# Iridium_Carrier_2.net
KiCad netlist of a schematic drawn in EAGLE
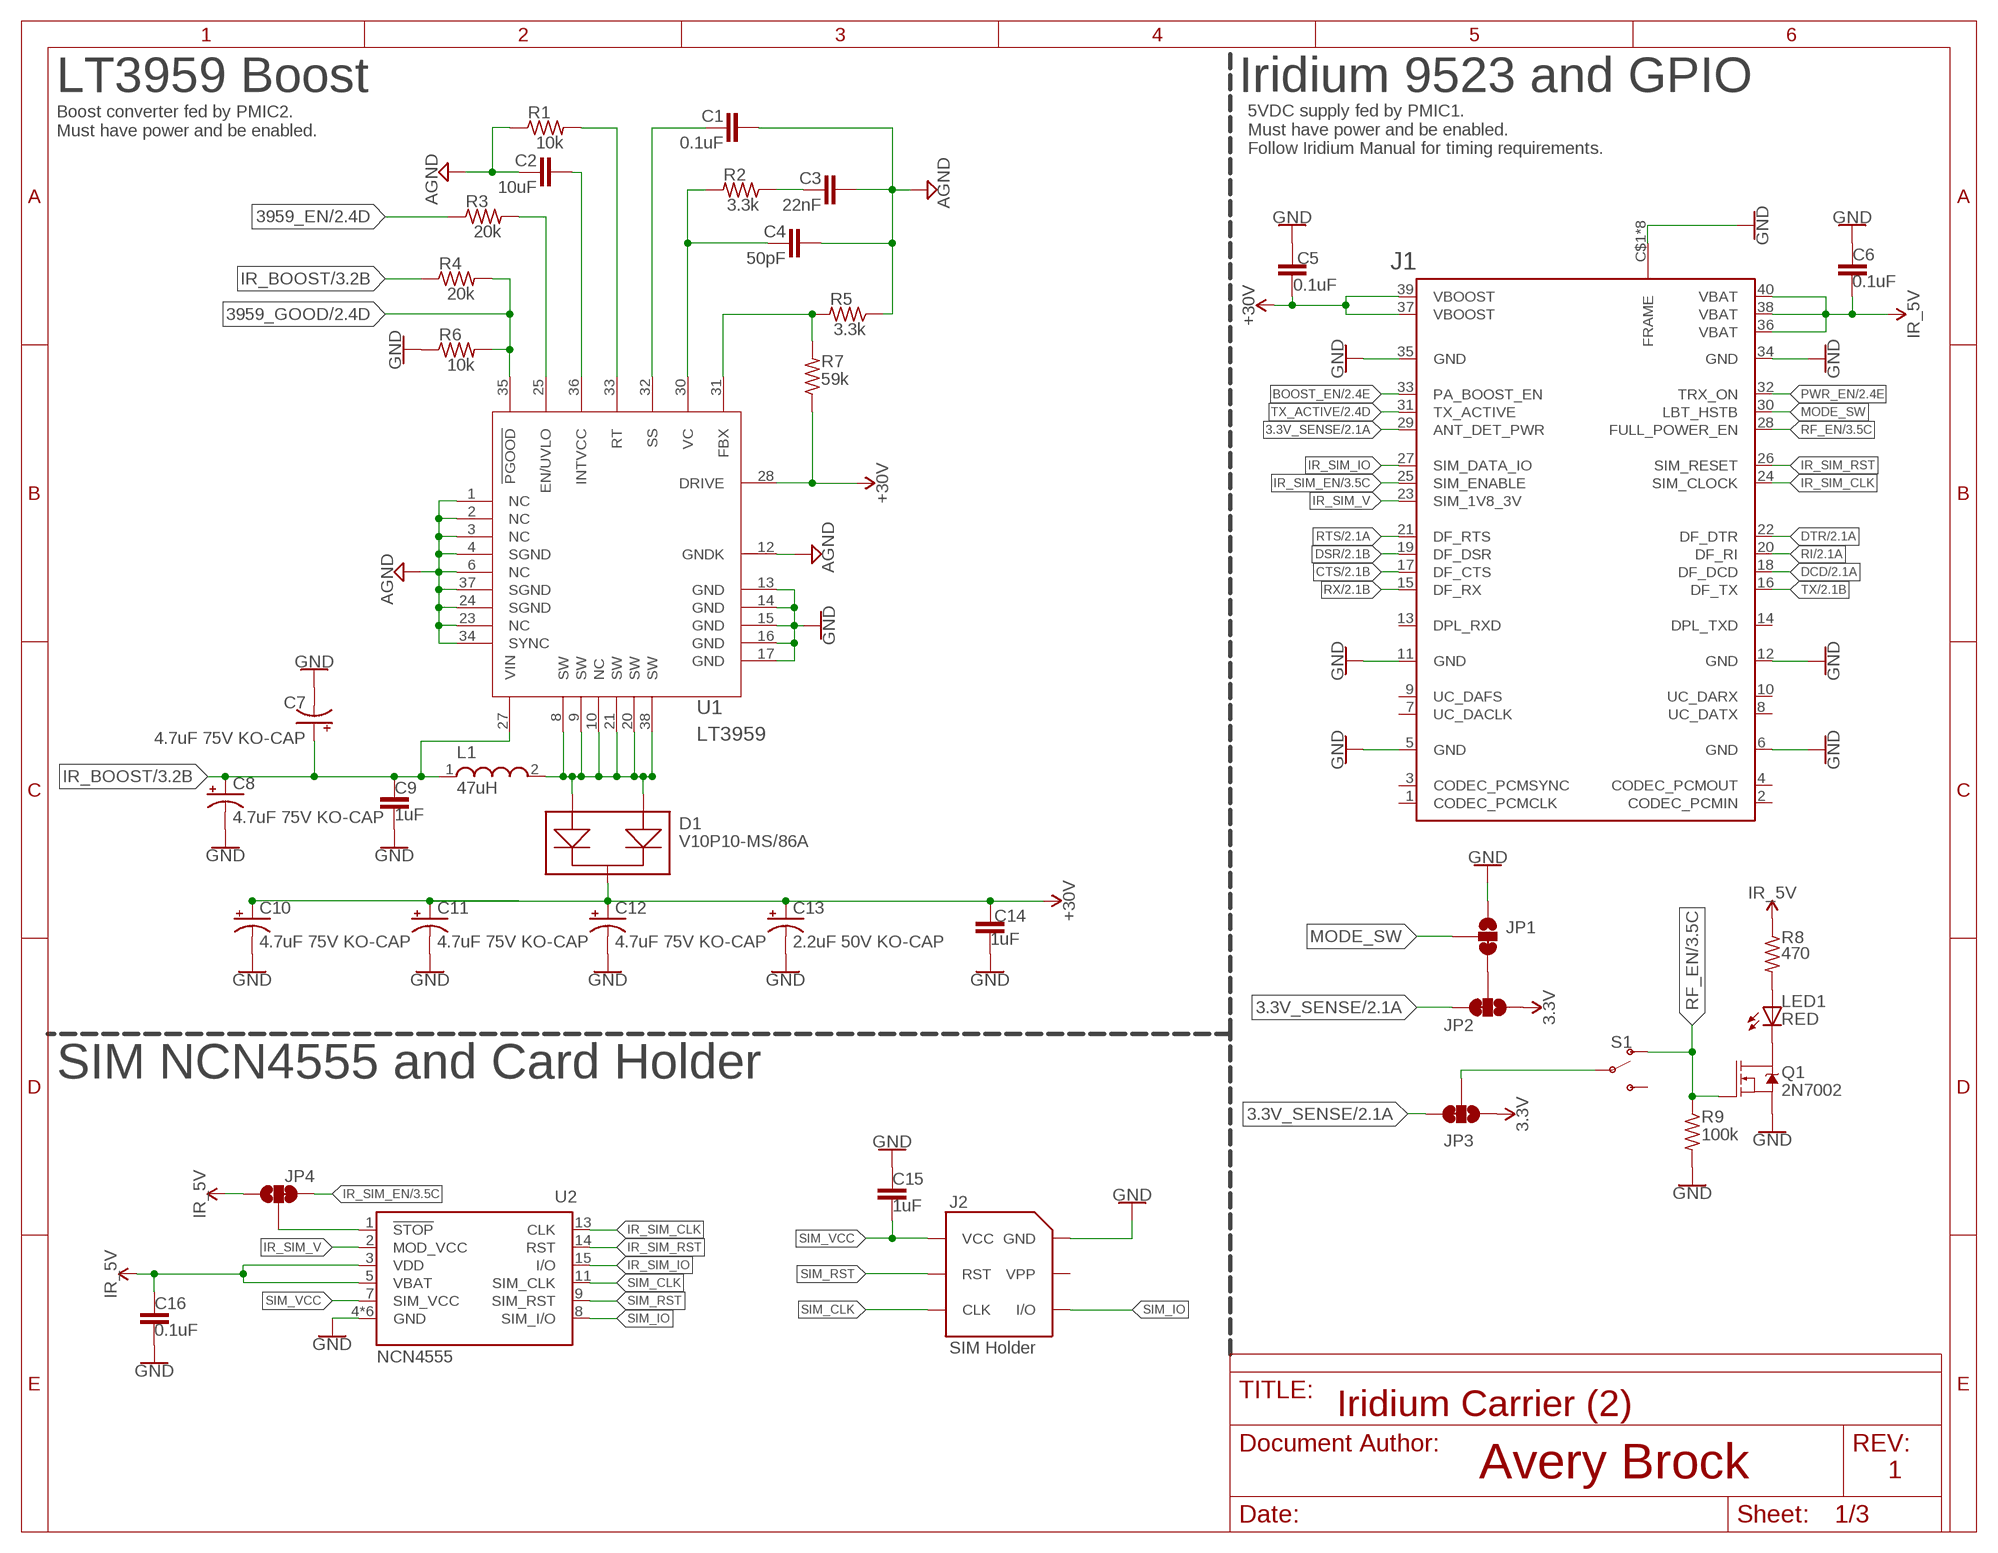
[diagram p0: schematic, sheet 1]
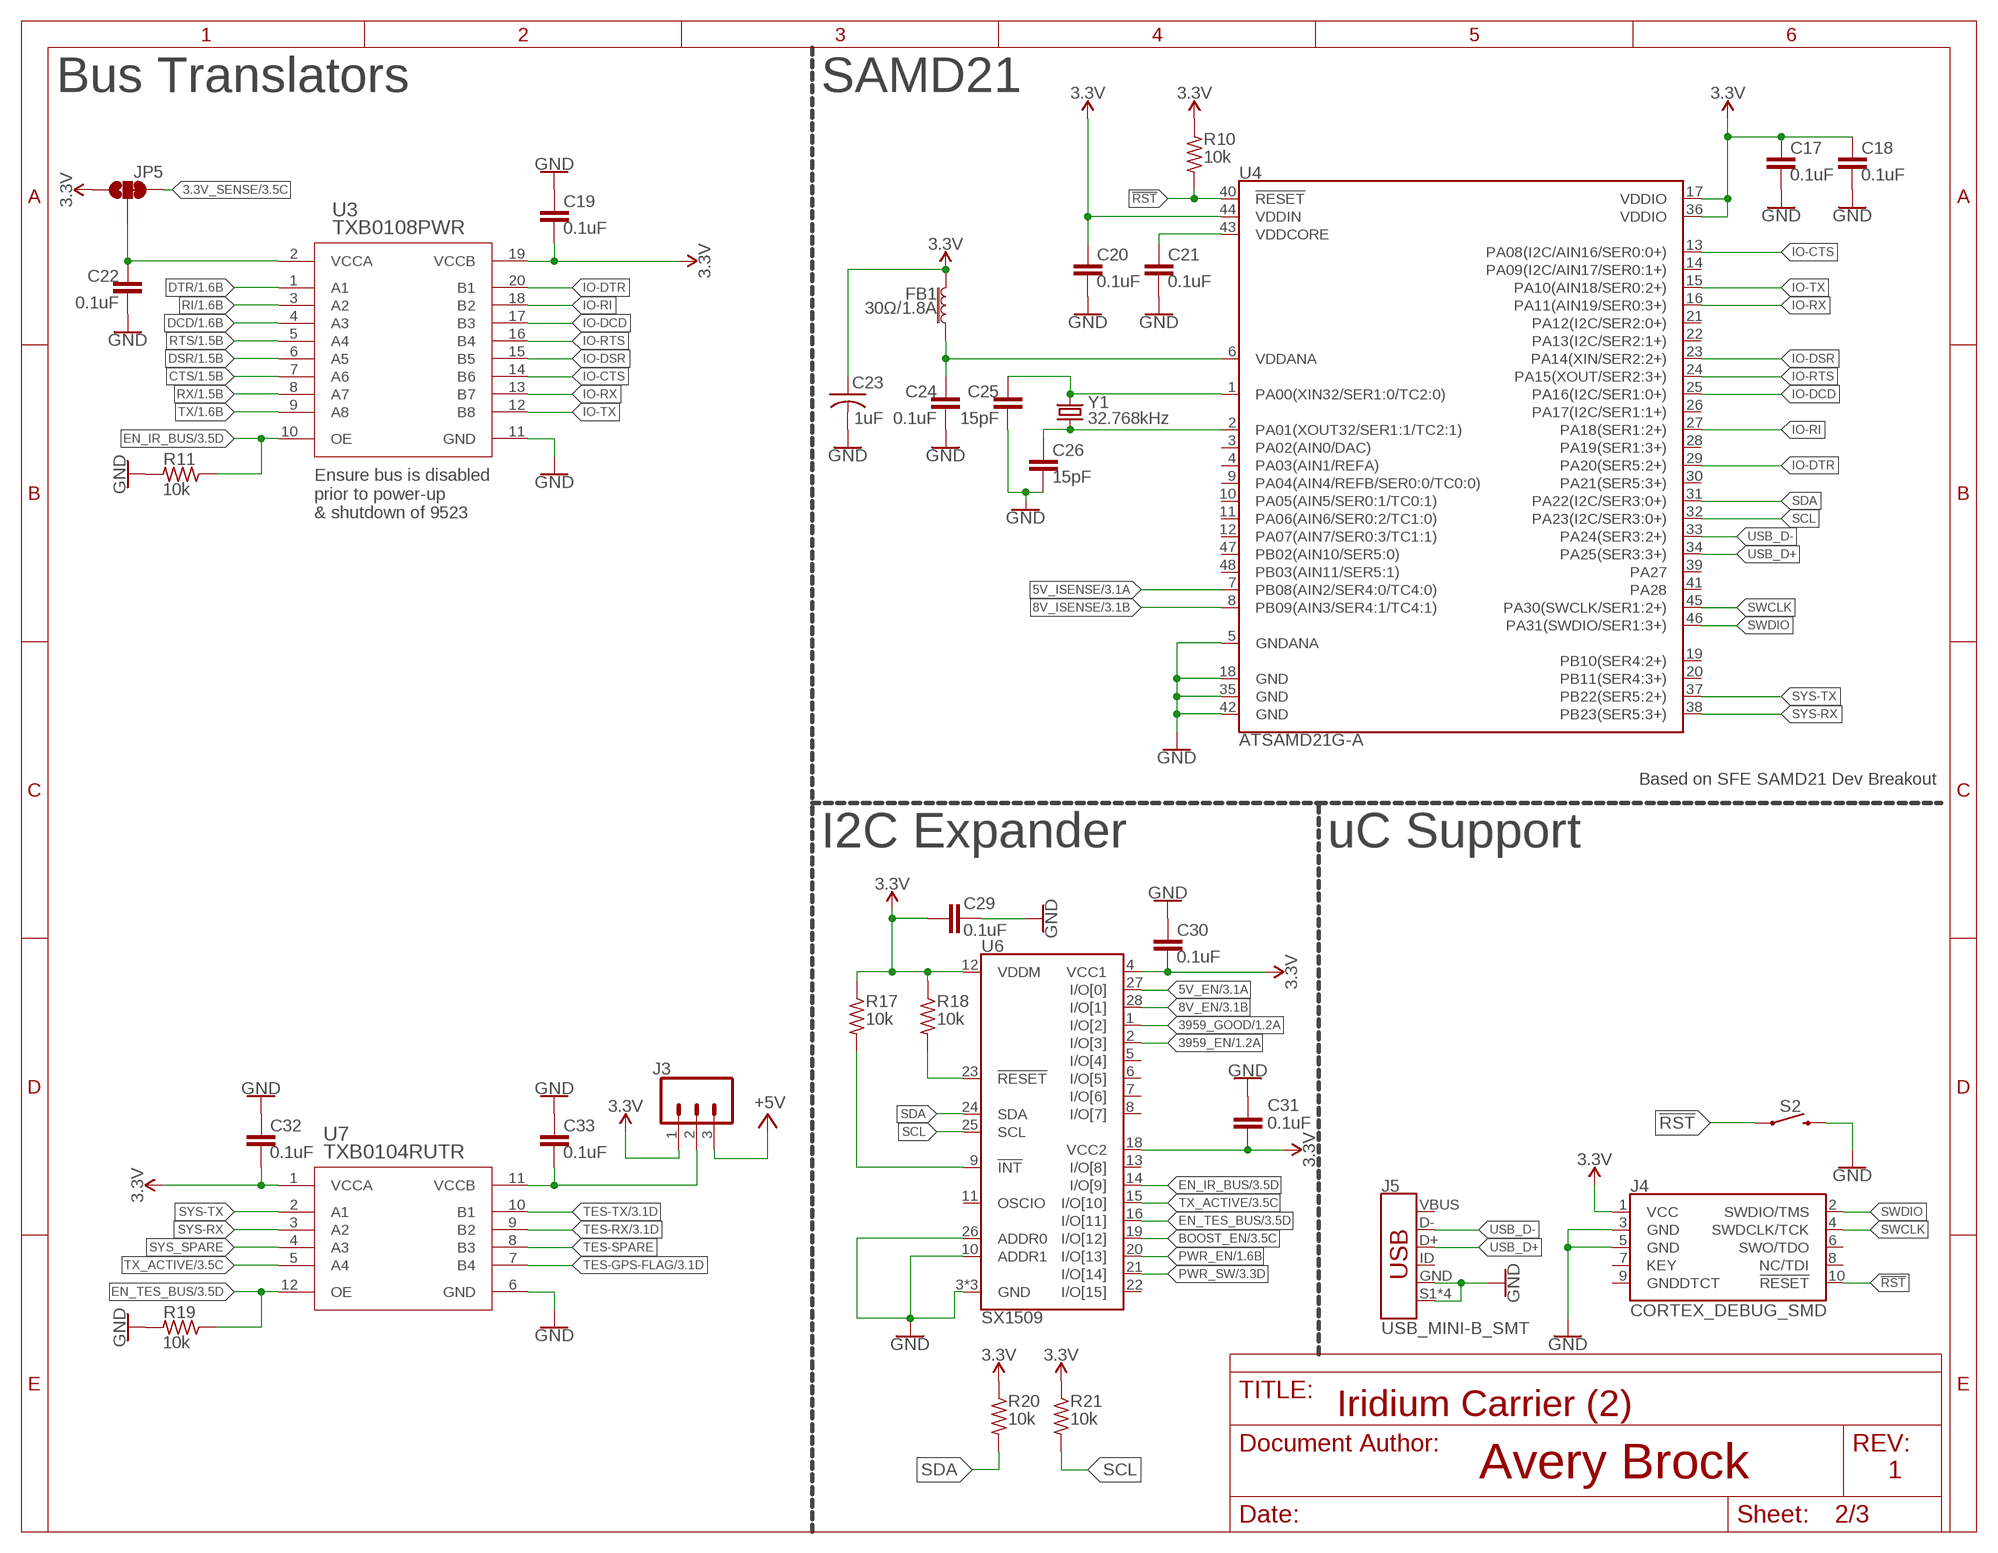
[diagram p1: schematic, sheet 2]
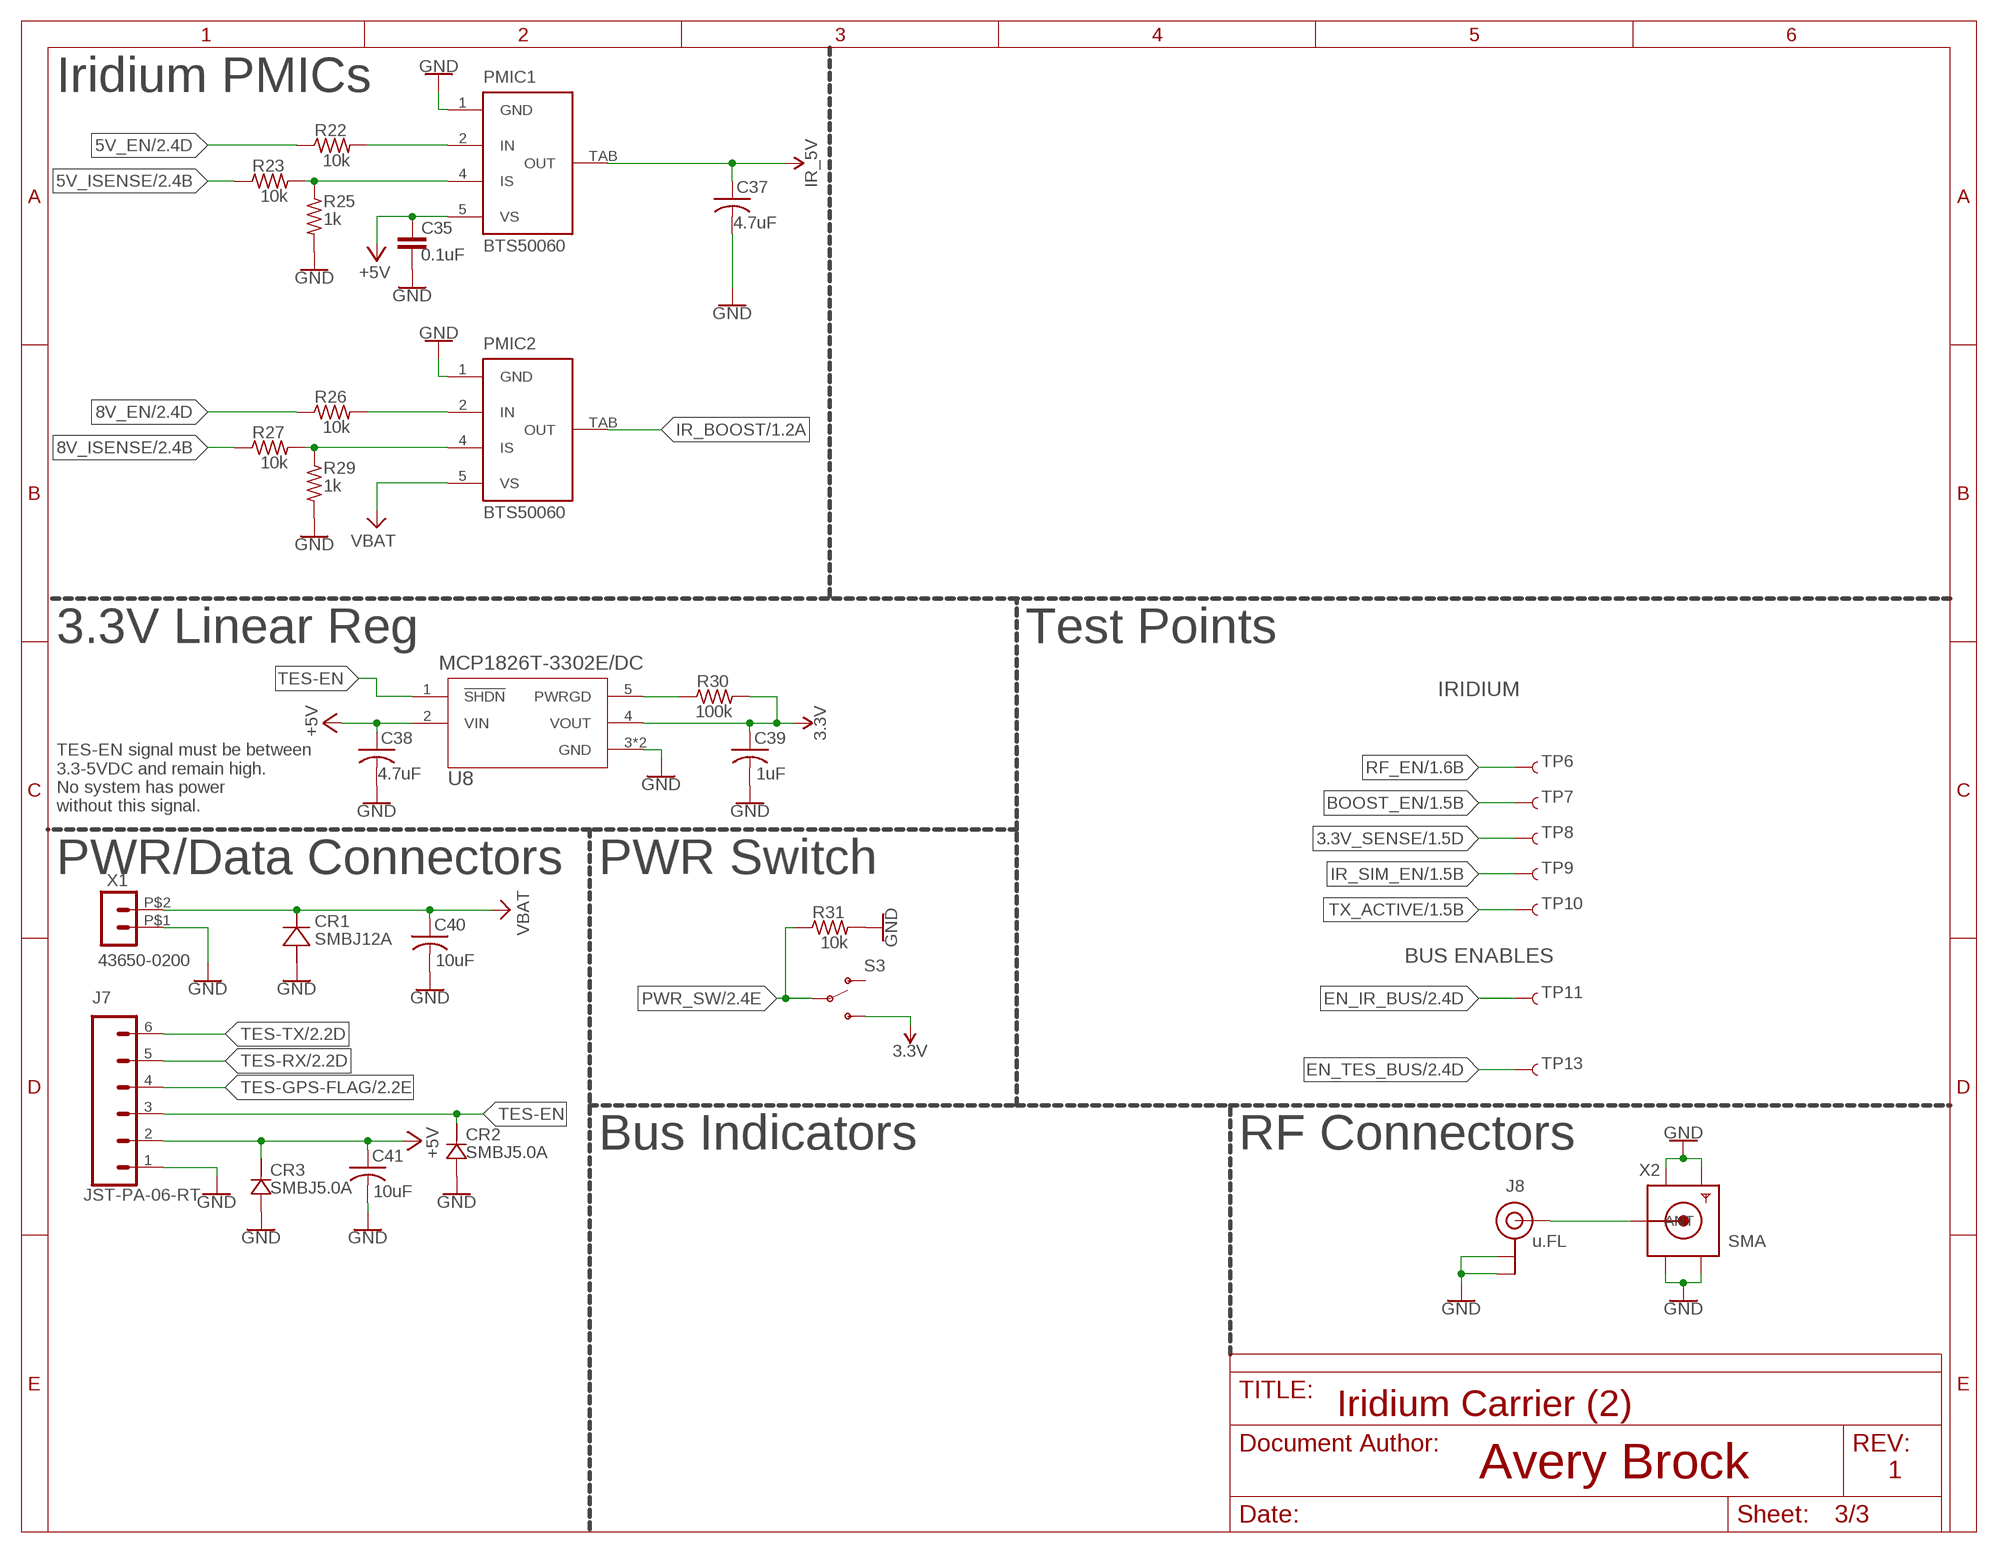
[diagram p2: schematic, sheet 3]

(export (version "E")
  (design (tool "Eeschema 10.0.6"))
  (components
    (comp (ref "C35")
      (value "0.1uF")
      (footprint "eagle-import:C0603")
      (libsource (lib "eagle-import") (part "C-EUC0603"))
    )
    (comp (ref "C37")
      (value "4.7uF")
      (footprint "eagle-import:C1206")
      (libsource (lib "eagle-import") (part "C-USC1206"))
    )
    (comp (ref "C38")
      (value "4.7uF")
      (footprint "eagle-import:C1206")
      (libsource (lib "eagle-import") (part "C-USC1206"))
    )
    (comp (ref "C39")
      (value "1uF")
      (footprint "eagle-import:C0805")
      (libsource (lib "eagle-import") (part "C-USC0805"))
    )
    (comp (ref "C40")
      (value "10uF")
      (footprint "eagle-import:C1206")
      (libsource (lib "eagle-import") (part "C-USC1206"))
    )
    (comp (ref "C41")
      (value "10uF")
      (footprint "eagle-import:C1206")
      (libsource (lib "eagle-import") (part "C-USC1206"))
    )
    (comp (ref "CR1")
      (value "SMBJ12A")
      (footprint "eagle-import:SMB")
      (libsource (lib "eagle-import") (part "SMBJ12A"))
    )
    (comp (ref "CR2")
      (value "SMBJ5.0A")
      (footprint "eagle-import:DIODE_DO214AA")
      (libsource (lib "eagle-import") (part "SMBJ5.0A"))
    )
    (comp (ref "CR3")
      (value "SMBJ5.0A")
      (footprint "eagle-import:DIODE_DO214AA")
      (libsource (lib "eagle-import") (part "SMBJ5.0A"))
    )
    (comp (ref "J7")
      (value "JST-PA-06-RT")
      (footprint "eagle-import:1X6-JST-PA")
      (libsource (lib "eagle-import") (part "JST-PA-06-RT"))
    )
    (comp (ref "J8")
      (value "U.FL")
      (footprint "eagle-import:U.FL")
      (libsource (lib "eagle-import") (part "U.FL"))
    )
    (comp (ref "PMIC1")
      (value "BTS50060")
      (footprint "eagle-import:TO252-5-11")
      (libsource (lib "eagle-import") (part "BTS50060"))
    )
    (comp (ref "PMIC2")
      (value "BTS50060")
      (footprint "eagle-import:TO252-5-11")
      (libsource (lib "eagle-import") (part "BTS50060"))
    )
    (comp (ref "R22")
      (value "10k")
      (footprint "eagle-import:R0603")
      (libsource (lib "eagle-import") (part "R-US_R0603"))
    )
    (comp (ref "R23")
      (value "10k")
      (footprint "eagle-import:R0603")
      (libsource (lib "eagle-import") (part "R-US_R0603"))
    )
    (comp (ref "R25")
      (value "1k")
      (footprint "eagle-import:R0603")
      (libsource (lib "eagle-import") (part "R-US_R0603"))
    )
    (comp (ref "R26")
      (value "10k")
      (footprint "eagle-import:R0603")
      (libsource (lib "eagle-import") (part "R-US_R0603"))
    )
    (comp (ref "R27")
      (value "10k")
      (footprint "eagle-import:R0603")
      (libsource (lib "eagle-import") (part "R-US_R0603"))
    )
    (comp (ref "R29")
      (value "1k")
      (footprint "eagle-import:R0603")
      (libsource (lib "eagle-import") (part "R-US_R0603"))
    )
    (comp (ref "R30")
      (value "100k")
      (footprint "eagle-import:R0603")
      (libsource (lib "eagle-import") (part "R-US_R0603"))
    )
    (comp (ref "R31")
      (value "10k")
      (footprint "eagle-import:R0603")
      (libsource (lib "eagle-import") (part "R-US_R0603"))
    )
    (comp (ref "S3")
      (value "PWR SW")
      (footprint "eagle-import:SWITCH_SPDT_PTH_11.6X4.0MM")
      (libsource (lib "eagle-import") (part "SWITCH-SPDT-PTH-11.6X4.0MM"))
    )
    (comp (ref "TP6")
      (value "TEST-POINT3X4")
      (footprint "eagle-import:PAD.03X.04")
      (libsource (lib "eagle-import") (part "TEST-POINT3X4"))
    )
    (comp (ref "TP7")
      (value "TEST-POINT3X4")
      (footprint "eagle-import:PAD.03X.04")
      (libsource (lib "eagle-import") (part "TEST-POINT3X4"))
    )
    (comp (ref "TP8")
      (value "TEST-POINT3X4")
      (footprint "eagle-import:PAD.03X.04")
      (libsource (lib "eagle-import") (part "TEST-POINT3X4"))
    )
    (comp (ref "TP9")
      (value "TEST-POINT3X4")
      (footprint "eagle-import:PAD.03X.04")
      (libsource (lib "eagle-import") (part "TEST-POINT3X4"))
    )
    (comp (ref "TP10")
      (value "TEST-POINT3X4")
      (footprint "eagle-import:PAD.03X.04")
      (libsource (lib "eagle-import") (part "TEST-POINT3X4"))
    )
    (comp (ref "TP11")
      (value "TEST-POINT3X4")
      (footprint "eagle-import:PAD.03X.04")
      (libsource (lib "eagle-import") (part "TEST-POINT3X4"))
    )
    (comp (ref "TP13")
      (value "TEST-POINT3X4")
      (footprint "eagle-import:PAD.03X.04")
      (libsource (lib "eagle-import") (part "TEST-POINT3X4"))
    )
    (comp (ref "U8")
      (value "MCP1826T-3302E/DC")
      (footprint "eagle-import:SOT-223_5MC")
      (fields (field (name "MANUFACTURER_PART_NUMBER") "MCP1826T3302EDC"))
      (libsource (lib "eagle-import") (part "MCP1826T-3302E/DC"))
    )
    (comp (ref "X1")
      (value "43650-0200")
      (footprint "eagle-import:43650-0200")
      (libsource (lib "eagle-import") (part "HEADER_POS2_?43650-0200"))
    )
    (comp (ref "X2")
      (value "SMACONNECTOR")
      (footprint "eagle-import:SMA90_DIP")
      (libsource (lib "eagle-import") (part "SMACONNECTOR"))
    )
    (comp (ref "C1")
      (value "0.1uF")
      (footprint "eagle-import:C0603")
      (libsource (lib "eagle-import") (part "C-EUC0603"))
    )
    (comp (ref "C2")
      (value "10uF")
      (footprint "eagle-import:C0603")
      (libsource (lib "eagle-import") (part "C-EUC0603"))
    )
    (comp (ref "C3")
      (value "22nF")
      (footprint "eagle-import:C0603")
      (libsource (lib "eagle-import") (part "C-EUC0603"))
    )
    (comp (ref "C4")
      (value "50pF")
      (footprint "eagle-import:C0603")
      (libsource (lib "eagle-import") (part "C-EUC0603"))
    )
    (comp (ref "C5")
      (value "0.1uF")
      (footprint "eagle-import:C0603")
      (libsource (lib "eagle-import") (part "C-EUC0603"))
    )
    (comp (ref "C6")
      (value "0.1uF")
      (footprint "eagle-import:C0603")
      (libsource (lib "eagle-import") (part "C-EUC0603"))
    )
    (comp (ref "C7")
      (value "4.7uF 75V KO-CAP")
      (footprint "eagle-import:D_7343-31R")
      (libsource (lib "eagle-import") (part "CPOL-USD/7343-31R"))
    )
    (comp (ref "C8")
      (value "4.7uF 75V KO-CAP")
      (footprint "eagle-import:D_7343-31R")
      (libsource (lib "eagle-import") (part "CPOL-USD/7343-31R"))
    )
    (comp (ref "C9")
      (value "1uF")
      (footprint "eagle-import:C0603")
      (libsource (lib "eagle-import") (part "C-EUC0603"))
    )
    (comp (ref "C10")
      (value "4.7uF 75V KO-CAP")
      (footprint "eagle-import:D_7343-31R")
      (libsource (lib "eagle-import") (part "CPOL-USD/7343-31R"))
    )
    (comp (ref "C11")
      (value "4.7uF 75V KO-CAP")
      (footprint "eagle-import:D_7343-31R")
      (libsource (lib "eagle-import") (part "CPOL-USD/7343-31R"))
    )
    (comp (ref "C12")
      (value "4.7uF 75V KO-CAP")
      (footprint "eagle-import:D_7343-31R")
      (libsource (lib "eagle-import") (part "CPOL-USD/7343-31R"))
    )
    (comp (ref "C13")
      (value "2.2uF 50V KO-CAP")
      (footprint "eagle-import:CT3528")
      (libsource (lib "eagle-import") (part "CPOL-USCT3528"))
    )
    (comp (ref "C14")
      (value "1uF")
      (footprint "eagle-import:C0603")
      (libsource (lib "eagle-import") (part "C-EUC0603"))
    )
    (comp (ref "C15")
      (value "1uF")
      (footprint "eagle-import:C0603")
      (libsource (lib "eagle-import") (part "C-EUC0603"))
    )
    (comp (ref "C16")
      (value "0.1uF")
      (footprint "eagle-import:C0603")
      (libsource (lib "eagle-import") (part "C-EUC0603"))
    )
    (comp (ref "D1")
      (value "V10P10-MS/86A")
      (footprint "eagle-import:DIODE_TO-277A")
      (libsource (lib "eagle-import") (part "V10P10-MS/86A"))
    )
    (comp (ref "J1")
      (value "Molex 0541020404")
      (footprint "eagle-import:IRIDIUM-9523")
      (libsource (lib "eagle-import") (part "IRIDIUM-9523DEFAULT"))
    )
    (comp (ref "J2")
      (value "SIM Holder")
      (footprint "eagle-import:SIMHOLDER")
      (libsource (lib "eagle-import") (part "SIMHOLDERSIM"))
    )
    (comp (ref "JP1")
      (value "OP MODE")
      (footprint "eagle-import:SMT-JUMPER_3_1-NC_TRACE_SILK")
      (libsource (lib "eagle-import") (part "JUMPER-SMT_3_1-NC_TRACE_SILK"))
    )
    (comp (ref "JP2")
      (value "Sense V")
      (footprint "eagle-import:SMT-JUMPER_3_1-NC_TRACE_SILK")
      (libsource (lib "eagle-import") (part "JUMPER-SMT_3_1-NC_TRACE_SILK"))
    )
    (comp (ref "JP3")
      (value "Sense V")
      (footprint "eagle-import:SMT-JUMPER_3_1-NC_TRACE_SILK")
      (libsource (lib "eagle-import") (part "JUMPER-SMT_3_1-NC_TRACE_SILK"))
    )
    (comp (ref "JP4")
      (value "SIM_STOP")
      (footprint "eagle-import:SMT-JUMPER_3_1-NC_TRACE_SILK")
      (libsource (lib "eagle-import") (part "JUMPER-SMT_3_1-NC_TRACE_SILK"))
    )
    (comp (ref "L1")
      (value "47uH")
      (footprint "eagle-import:WE-HCI_1890")
      (libsource (lib "eagle-import") (part "WE-HCI_1890"))
    )
    (comp (ref "LED1")
      (value "RED")
      (footprint "eagle-import:CHIP-LED0805")
      (libsource (lib "eagle-import") (part "LEDCHIP-LED0805"))
    )
    (comp (ref "Q1")
      (value "2N7002")
      (footprint "eagle-import:SOT23-3")
      (libsource (lib "eagle-import") (part "MOSFET-NCH-AO3404A"))
    )
    (comp (ref "R1")
      (value "10k")
      (footprint "eagle-import:R0603")
      (libsource (lib "eagle-import") (part "R-US_R0603"))
    )
    (comp (ref "R2")
      (value "3.3k")
      (footprint "eagle-import:R0603")
      (libsource (lib "eagle-import") (part "R-US_R0603"))
    )
    (comp (ref "R3")
      (value "20k")
      (footprint "eagle-import:R0603")
      (libsource (lib "eagle-import") (part "R-US_R0603"))
    )
    (comp (ref "R4")
      (value "20k")
      (footprint "eagle-import:R0603")
      (libsource (lib "eagle-import") (part "R-US_R0603"))
    )
    (comp (ref "R5")
      (value "3.3k")
      (footprint "eagle-import:R0603")
      (libsource (lib "eagle-import") (part "R-US_R0603"))
    )
    (comp (ref "R6")
      (value "10k")
      (footprint "eagle-import:R0603")
      (libsource (lib "eagle-import") (part "R-US_R0603"))
    )
    (comp (ref "R7")
      (value "59k")
      (footprint "eagle-import:R0603")
      (libsource (lib "eagle-import") (part "R-US_R0603"))
    )
    (comp (ref "R8")
      (value "470")
      (footprint "eagle-import:R0603")
      (libsource (lib "eagle-import") (part "R-US_R0603"))
    )
    (comp (ref "R9")
      (value "100k")
      (footprint "eagle-import:R0603")
      (libsource (lib "eagle-import") (part "R-US_R0603"))
    )
    (comp (ref "S1")
      (value "FULL RF PWR")
      (footprint "eagle-import:SWITCH_SPDT_PTH_11.6X4.0MM")
      (libsource (lib "eagle-import") (part "SWITCH-SPDT-PTH-11.6X4.0MM"))
    )
    (comp (ref "U1")
      (value "LT3959")
      (footprint "eagle-import:QFN-36_UHEMA")
      (libsource (lib "eagle-import") (part "LT3959"))
    )
    (comp (ref "U2")
      (value "DAVID-HANDY_ON_NCN4555DEFAULT")
      (footprint "eagle-import:DAVID-HANDY_QFN16-3X3MM")
      (fields (field (name "SPICEPREFIX") "X"))
      (libsource (lib "eagle-import") (part "DAVID-HANDY_ON_NCN4555DEFAULT"))
    )
    (comp (ref "C17")
      (value "0.1uF")
      (footprint "eagle-import:C0603")
      (libsource (lib "eagle-import") (part "C-EUC0603"))
    )
    (comp (ref "C18")
      (value "0.1uF")
      (footprint "eagle-import:C0603")
      (libsource (lib "eagle-import") (part "C-EUC0603"))
    )
    (comp (ref "C19")
      (value "0.1uF")
      (footprint "eagle-import:C0603")
      (libsource (lib "eagle-import") (part "C-EUC0603"))
    )
    (comp (ref "C20")
      (value "0.1uF")
      (footprint "eagle-import:C0603")
      (libsource (lib "eagle-import") (part "C-EUC0603"))
    )
    (comp (ref "C21")
      (value "0.1uF")
      (footprint "eagle-import:C0603")
      (libsource (lib "eagle-import") (part "C-EUC0603"))
    )
    (comp (ref "C22")
      (value "0.1uF")
      (footprint "eagle-import:C0603")
      (libsource (lib "eagle-import") (part "C-EUC0603"))
    )
    (comp (ref "C23")
      (value "1uF")
      (footprint "eagle-import:C0805")
      (libsource (lib "eagle-import") (part "C-USC0805"))
    )
    (comp (ref "C24")
      (value "0.1uF")
      (footprint "eagle-import:C0603")
      (libsource (lib "eagle-import") (part "C-EUC0603"))
    )
    (comp (ref "C25")
      (value "15pF")
      (footprint "eagle-import:C0603")
      (libsource (lib "eagle-import") (part "C-EUC0603"))
    )
    (comp (ref "C26")
      (value "15pF")
      (footprint "eagle-import:C0603")
      (libsource (lib "eagle-import") (part "C-EUC0603"))
    )
    (comp (ref "C29")
      (value "0.1uF")
      (footprint "eagle-import:C0603")
      (libsource (lib "eagle-import") (part "C-EUC0603"))
    )
    (comp (ref "C30")
      (value "0.1uF")
      (footprint "eagle-import:C0603")
      (libsource (lib "eagle-import") (part "C-EUC0603"))
    )
    (comp (ref "C31")
      (value "0.1uF")
      (footprint "eagle-import:C0603")
      (libsource (lib "eagle-import") (part "C-EUC0603"))
    )
    (comp (ref "C32")
      (value "0.1uF")
      (footprint "eagle-import:C0603")
      (libsource (lib "eagle-import") (part "C-EUC0603"))
    )
    (comp (ref "C33")
      (value "0.1uF")
      (footprint "eagle-import:C0603")
      (libsource (lib "eagle-import") (part "C-EUC0603"))
    )
    (comp (ref "FB1")
      (value "30Ω/1.8A")
      (footprint "eagle-import:0603")
      (libsource (lib "eagle-import") (part "FERRITE_BEAD-0603"))
    )
    (comp (ref "J3")
      (value "455-1750-1-ND")
      (footprint "eagle-import:1X03")
      (libsource (lib "eagle-import") (part "CONN_03"))
    )
    (comp (ref "J4")
      (value "CORTEX_DEBUG_SMD")
      (footprint "eagle-import:SAMTECH_FTSH-105-01")
      (libsource (lib "eagle-import") (part "CORTEX_DEBUG_SMD"))
    )
    (comp (ref "J5")
      (value "USB_MINI-B_SMT")
      (footprint "eagle-import:USB-MINIB")
      (libsource (lib "eagle-import") (part "USB_MINI-B_SMT"))
    )
    (comp (ref "JP5")
      (value "BUS_V")
      (footprint "eagle-import:SMT-JUMPER_3_1-NC_TRACE_SILK")
      (libsource (lib "eagle-import") (part "JUMPER-SMT_3_1-NC_TRACE_SILK"))
    )
    (comp (ref "R10")
      (value "10k")
      (footprint "eagle-import:R0603")
      (libsource (lib "eagle-import") (part "R-US_R0603"))
    )
    (comp (ref "R11")
      (value "10k")
      (footprint "eagle-import:R0603")
      (libsource (lib "eagle-import") (part "R-US_R0603"))
    )
    (comp (ref "R17")
      (value "10k")
      (footprint "eagle-import:R0603")
      (libsource (lib "eagle-import") (part "R-US_R0603"))
    )
    (comp (ref "R18")
      (value "10k")
      (footprint "eagle-import:R0603")
      (libsource (lib "eagle-import") (part "R-US_R0603"))
    )
    (comp (ref "R19")
      (value "10k")
      (footprint "eagle-import:R0603")
      (libsource (lib "eagle-import") (part "R-US_R0603"))
    )
    (comp (ref "R20")
      (value "10k")
      (footprint "eagle-import:R0603")
      (libsource (lib "eagle-import") (part "R-US_R0603"))
    )
    (comp (ref "R21")
      (value "10k")
      (footprint "eagle-import:R0603")
      (libsource (lib "eagle-import") (part "R-US_R0603"))
    )
    (comp (ref "S2")
      (value "RST BTN")
      (footprint "eagle-import:TACTILE_SWITCH_SMD_6.0X3.5MM")
      (libsource (lib "eagle-import") (part "MOMENTARY-SWITCH-SPST-SMD-6.0X3.5MM"))
    )
    (comp (ref "U3")
      (value "TXB0108PWR")
      (footprint "eagle-import:PW20")
      (libsource (lib "eagle-import") (part "TXB0108PWR"))
    )
    (comp (ref "U4")
      (value "ATSAMD21G-A")
      (footprint "eagle-import:TQFP-48")
      (libsource (lib "eagle-import") (part "ATSAMD21G-A"))
    )
    (comp (ref "U6")
      (value "SX1509")
      (footprint "eagle-import:QFN-28")
      (libsource (lib "eagle-import") (part "SX1509"))
    )
    (comp (ref "U7")
      (value "TXB0104RUTR")
      (footprint "eagle-import:RUT12")
      (libsource (lib "eagle-import") (part "TXB0104RUTR"))
    )
    (comp (ref "Y1")
      (value "32.768kHz")
      (footprint "eagle-import:CRYSTAL-SMD-3.2X1.5MM")
      (libsource (lib "eagle-import") (part "CRYSTAL-32.768KHZSMD-3.2X1.5"))
    )
  )
  (nets
    (net (code "1") (name "+5V") (class "Default")
      (node (ref "C35") (pin "1") (pinfunction "1_1") (pintype "passive"))
      (node (ref "C38") (pin "1") (pinfunction "1_1") (pintype "passive"))
      (node (ref "C41") (pin "1") (pinfunction "1_1") (pintype "passive"))
      (node (ref "CR3") (pin "1") (pinfunction "2_1") (pintype "passive"))
      (node (ref "J3") (pin "3") (pinfunction "3_3") (pintype "passive"))
      (node (ref "J7") (pin "2") (pinfunction "2_2") (pintype "passive"))
      (node (ref "PMIC1") (pin "5") (pinfunction "VS_5") (pintype "bidirectional"))
      (node (ref "U8") (pin "2") (pinfunction "VIN_2") (pintype "passive"))
    )
    (net (code "2") (name "3.3V") (class "Default")
      (node (ref "C17") (pin "1") (pinfunction "1_1") (pintype "passive"))
      (node (ref "C18") (pin "1") (pinfunction "1_1") (pintype "passive"))
      (node (ref "C19") (pin "2") (pinfunction "2_2") (pintype "passive"))
      (node (ref "C20") (pin "1") (pinfunction "1_1") (pintype "passive"))
      (node (ref "C23") (pin "1") (pinfunction "1_1") (pintype "passive"))
      (node (ref "C29") (pin "1") (pinfunction "1_1") (pintype "passive"))
      (node (ref "C30") (pin "2") (pinfunction "2_2") (pintype "passive"))
      (node (ref "C31") (pin "2") (pinfunction "2_2") (pintype "passive"))
      (node (ref "C32") (pin "2") (pinfunction "2_2") (pintype "passive"))
      (node (ref "C39") (pin "1") (pinfunction "1_1") (pintype "passive"))
      (node (ref "FB1") (pin "2") (pinfunction "2_2") (pintype "passive"))
      (node (ref "J3") (pin "1") (pinfunction "1_1") (pintype "passive"))
      (node (ref "J4") (pin "1") (pinfunction "VCC_1") (pintype "bidirectional"))
      (node (ref "JP2") (pin "1") (pinfunction "1_1") (pintype "passive"))
      (node (ref "JP3") (pin "1") (pinfunction "1_1") (pintype "passive"))
      (node (ref "JP5") (pin "1") (pinfunction "1_1") (pintype "passive"))
      (node (ref "R10") (pin "1") (pinfunction "1_1") (pintype "passive"))
      (node (ref "R17") (pin "1") (pinfunction "1_1") (pintype "passive"))
      (node (ref "R18") (pin "1") (pinfunction "1_1") (pintype "passive"))
      (node (ref "R20") (pin "1") (pinfunction "1_1") (pintype "passive"))
      (node (ref "R21") (pin "1") (pinfunction "1_1") (pintype "passive"))
      (node (ref "R30") (pin "2") (pinfunction "2_2") (pintype "passive"))
      (node (ref "S3") (pin "3") (pinfunction "S_3") (pintype "passive"))
      (node (ref "U3") (pin "19") (pinfunction "VCCB_19") (pintype "power_in"))
      (node (ref "U4") (pin "17") (pinfunction "VDDIO_17") (pintype "bidirectional"))
      (node (ref "U4") (pin "36") (pinfunction "VDDIO_36") (pintype "bidirectional"))
      (node (ref "U4") (pin "44") (pinfunction "VDDIN_44") (pintype "bidirectional"))
      (node (ref "U6") (pin "12") (pinfunction "VDDM_12") (pintype "bidirectional"))
      (node (ref "U6") (pin "18") (pinfunction "VCC2_18") (pintype "bidirectional"))
      (node (ref "U6") (pin "4") (pinfunction "VCC1_4") (pintype "bidirectional"))
      (node (ref "U7") (pin "1") (pinfunction "VCCA_1") (pintype "power_in"))
      (node (ref "U8") (pin "4") (pinfunction "VOUT_4") (pintype "passive"))
    )
    (net (code "3") (name "3.3V_SENSE") (class "Default")
      (node (ref "J1") (pin "29") (pinfunction "ANT_DET_PWR_29") (pintype "bidirectional"))
      (node (ref "JP2") (pin "3") (pinfunction "3_3") (pintype "passive"))
      (node (ref "JP3") (pin "3") (pinfunction "3_3") (pintype "passive"))
      (node (ref "JP5") (pin "3") (pinfunction "3_3") (pintype "passive"))
      (node (ref "TP8") (pin "P$1") (pinfunction "1_P$1") (pintype "bidirectional"))
    )
    (net (code "4") (name "5V_EN") (class "Default")
      (node (ref "R22") (pin "1") (pinfunction "1_1") (pintype "passive"))
      (node (ref "U6") (pin "27") (pinfunction "I/O[0]_27") (pintype "bidirectional"))
    )
    (net (code "5") (name "5V_ISENSE") (class "Default")
      (node (ref "R23") (pin "1") (pinfunction "1_1") (pintype "passive"))
      (node (ref "U4") (pin "7") (pinfunction "PB08(AIN2/SER4:0/TC4:0)_7") (pintype "bidirectional"))
    )
    (net (code "6") (name "8V_EN") (class "Default")
      (node (ref "R26") (pin "1") (pinfunction "1_1") (pintype "passive"))
      (node (ref "U6") (pin "28") (pinfunction "I/O[1]_28") (pintype "bidirectional"))
    )
    (net (code "7") (name "8V_ISENSE") (class "Default")
      (node (ref "R27") (pin "1") (pinfunction "1_1") (pintype "passive"))
      (node (ref "U4") (pin "8") (pinfunction "PB09(AIN3/SER4:1/TC4:1)_8") (pintype "bidirectional"))
    )
    (net (code "8") (name "3959_EN") (class "Default")
      (node (ref "R3") (pin "1") (pinfunction "1_1") (pintype "passive"))
      (node (ref "U6") (pin "2") (pinfunction "I/O[3]_2") (pintype "bidirectional"))
    )
    (net (code "9") (name "3959_GOOD") (class "Default")
      (node (ref "R4") (pin "2") (pinfunction "2_2") (pintype "passive"))
      (node (ref "R6") (pin "2") (pinfunction "2_2") (pintype "passive"))
      (node (ref "U1") (pin "35") (pinfunction "~{PGOOD}_35") (pintype "passive"))
      (node (ref "U6") (pin "1") (pinfunction "I/O[2]_1") (pintype "bidirectional"))
    )
    (net (code "10") (name "AGND") (class "Default")
      (node (ref "C1") (pin "2") (pinfunction "2_2") (pintype "passive"))
      (node (ref "C2") (pin "1") (pinfunction "1_1") (pintype "passive"))
      (node (ref "C3") (pin "2") (pinfunction "2_2") (pintype "passive"))
      (node (ref "C4") (pin "2") (pinfunction "2_2") (pintype "passive"))
      (node (ref "R1") (pin "1") (pinfunction "1_1") (pintype "passive"))
      (node (ref "R5") (pin "1") (pinfunction "1_1") (pintype "passive"))
      (node (ref "U1") (pin "1") (pinfunction "NC_1") (pintype "passive"))
      (node (ref "U1") (pin "12") (pinfunction "GNDK_12") (pintype "passive"))
      (node (ref "U1") (pin "2") (pinfunction "NC_2") (pintype "passive"))
      (node (ref "U1") (pin "23") (pinfunction "NC_23") (pintype "passive"))
      (node (ref "U1") (pin "24") (pinfunction "SGND_24") (pintype "passive"))
      (node (ref "U1") (pin "3") (pinfunction "NC_3") (pintype "passive"))
      (node (ref "U1") (pin "34") (pinfunction "SYNC_34") (pintype "passive"))
      (node (ref "U1") (pin "37") (pinfunction "SGND_37") (pintype "passive"))
      (node (ref "U1") (pin "4") (pinfunction "SGND_4") (pintype "passive"))
      (node (ref "U1") (pin "6") (pinfunction "NC_6") (pintype "passive"))
    )
    (net (code "11") (name "BOOST_EN") (class "Default")
      (node (ref "J1") (pin "33") (pinfunction "PA_BOOST_EN_33") (pintype "bidirectional"))
      (node (ref "TP7") (pin "P$1") (pinfunction "1_P$1") (pintype "bidirectional"))
      (node (ref "U6") (pin "19") (pinfunction "I/O[12]_19") (pintype "bidirectional"))
    )
    (net (code "12") (name "CTS") (class "Default")
      (node (ref "J1") (pin "17") (pinfunction "DF_CTS_17") (pintype "bidirectional"))
      (node (ref "U3") (pin "7") (pinfunction "A6_7") (pintype "bidirectional"))
    )
    (net (code "13") (name "DCD") (class "Default")
      (node (ref "J1") (pin "18") (pinfunction "DF_DCD_18") (pintype "bidirectional"))
      (node (ref "U3") (pin "4") (pinfunction "A3_4") (pintype "bidirectional"))
    )
    (net (code "14") (name "DSR") (class "Default")
      (node (ref "J1") (pin "19") (pinfunction "DF_DSR_19") (pintype "bidirectional"))
      (node (ref "U3") (pin "6") (pinfunction "A5_6") (pintype "bidirectional"))
    )
    (net (code "15") (name "DTR") (class "Default")
      (node (ref "J1") (pin "22") (pinfunction "DF_DTR_22") (pintype "bidirectional"))
      (node (ref "U3") (pin "1") (pinfunction "A1_1") (pintype "bidirectional"))
    )
    (net (code "16") (name "EN_IR_BUS") (class "Default")
      (node (ref "R11") (pin "1") (pinfunction "1_1") (pintype "passive"))
      (node (ref "TP11") (pin "P$1") (pinfunction "1_P$1") (pintype "bidirectional"))
      (node (ref "U3") (pin "10") (pinfunction "OE_10") (pintype "output"))
      (node (ref "U6") (pin "14") (pinfunction "I/O[9]_14") (pintype "bidirectional"))
    )
    (net (code "17") (name "EN_TES_BUS") (class "Default")
      (node (ref "R19") (pin "1") (pinfunction "1_1") (pintype "passive"))
      (node (ref "TP13") (pin "P$1") (pinfunction "1_P$1") (pintype "bidirectional"))
      (node (ref "U6") (pin "16") (pinfunction "I/O[11]_16") (pintype "bidirectional"))
      (node (ref "U7") (pin "12") (pinfunction "OE_12") (pintype "output"))
    )
    (net (code "18") (name "GND") (class "Default")
      (node (ref "C10") (pin "-") (pinfunction "-_-") (pintype "passive"))
      (node (ref "C11") (pin "-") (pinfunction "-_-") (pintype "passive"))
      (node (ref "C12") (pin "-") (pinfunction "-_-") (pintype "passive"))
      (node (ref "C13") (pin "-") (pinfunction "-_-") (pintype "passive"))
      (node (ref "C14") (pin "2") (pinfunction "2_2") (pintype "passive"))
      (node (ref "C15") (pin "1") (pinfunction "1_1") (pintype "passive"))
      (node (ref "C16") (pin "1") (pinfunction "1_1") (pintype "passive"))
      (node (ref "C17") (pin "2") (pinfunction "2_2") (pintype "passive"))
      (node (ref "C18") (pin "2") (pinfunction "2_2") (pintype "passive"))
      (node (ref "C19") (pin "1") (pinfunction "1_1") (pintype "passive"))
      (node (ref "C20") (pin "2") (pinfunction "2_2") (pintype "passive"))
      (node (ref "C21") (pin "2") (pinfunction "2_2") (pintype "passive"))
      (node (ref "C22") (pin "1") (pinfunction "1_1") (pintype "passive"))
      (node (ref "C23") (pin "2") (pinfunction "2_2") (pintype "passive"))
      (node (ref "C24") (pin "2") (pinfunction "2_2") (pintype "passive"))
      (node (ref "C25") (pin "2") (pinfunction "2_2") (pintype "passive"))
      (node (ref "C26") (pin "2") (pinfunction "2_2") (pintype "passive"))
      (node (ref "C29") (pin "2") (pinfunction "2_2") (pintype "passive"))
      (node (ref "C30") (pin "1") (pinfunction "1_1") (pintype "passive"))
      (node (ref "C31") (pin "1") (pinfunction "1_1") (pintype "passive"))
      (node (ref "C32") (pin "1") (pinfunction "1_1") (pintype "passive"))
      (node (ref "C33") (pin "1") (pinfunction "1_1") (pintype "passive"))
      (node (ref "C35") (pin "2") (pinfunction "2_2") (pintype "passive"))
      (node (ref "C37") (pin "2") (pinfunction "2_2") (pintype "passive"))
      (node (ref "C38") (pin "2") (pinfunction "2_2") (pintype "passive"))
      (node (ref "C39") (pin "2") (pinfunction "2_2") (pintype "passive"))
      (node (ref "C40") (pin "2") (pinfunction "2_2") (pintype "passive"))
      (node (ref "C41") (pin "2") (pinfunction "2_2") (pintype "passive"))
      (node (ref "C5") (pin "1") (pinfunction "1_1") (pintype "passive"))
      (node (ref "C6") (pin "1") (pinfunction "1_1") (pintype "passive"))
      (node (ref "C7") (pin "-") (pinfunction "-_-") (pintype "passive"))
      (node (ref "C8") (pin "-") (pinfunction "-_-") (pintype "passive"))
      (node (ref "C9") (pin "2") (pinfunction "2_2") (pintype "passive"))
      (node (ref "CR1") (pin "2") (pinfunction "CATHODE2_2") (pintype "passive"))
      (node (ref "CR2") (pin "2") (pinfunction "1_2") (pintype "passive"))
      (node (ref "CR3") (pin "2") (pinfunction "1_2") (pintype "passive"))
      (node (ref "J1") (pin "11") (pinfunction "GND_11") (pintype "bidirectional"))
      (node (ref "J1") (pin "12") (pinfunction "GND_12") (pintype "bidirectional"))
      (node (ref "J1") (pin "34") (pinfunction "GND_34") (pintype "bidirectional"))
      (node (ref "J1") (pin "35") (pinfunction "GND_35") (pintype "bidirectional"))
      (node (ref "J1") (pin "5") (pinfunction "GND_5") (pintype "bidirectional"))
      (node (ref "J1") (pin "6") (pinfunction "GND_6") (pintype "bidirectional"))
      (node (ref "J1") (pin "C$1") (pinfunction "FRAME_C$1") (pintype "bidirectional"))
      (node (ref "J1") (pin "C$2") (pinfunction "FRAME_C$2") (pintype "bidirectional"))
      (node (ref "J1") (pin "C$3") (pinfunction "FRAME_C$3") (pintype "bidirectional"))
      (node (ref "J1") (pin "C$4") (pinfunction "FRAME_C$4") (pintype "bidirectional"))
      (node (ref "J1") (pin "C$5") (pinfunction "FRAME_C$5") (pintype "bidirectional"))
      (node (ref "J1") (pin "C$6") (pinfunction "FRAME_C$6") (pintype "bidirectional"))
      (node (ref "J1") (pin "C$7") (pinfunction "FRAME_C$7") (pintype "bidirectional"))
      (node (ref "J1") (pin "C$8") (pinfunction "FRAME_C$8") (pintype "bidirectional"))
      (node (ref "J2") (pin "C5") (pinfunction "GND_C5") (pintype "power_in"))
      (node (ref "J4") (pin "3") (pinfunction "GND_3") (pintype "bidirectional"))
      (node (ref "J4") (pin "5") (pinfunction "GND_5") (pintype "bidirectional"))
      (node (ref "J5") (pin "GND") (pinfunction "GND_GND") (pintype "power_in"))
      (node (ref "J5") (pin "S1") (pinfunction "SHIELD_S1") (pintype "bidirectional"))
      (node (ref "J5") (pin "S2") (pinfunction "SHIELD_S2") (pintype "bidirectional"))
      (node (ref "J5") (pin "S3") (pinfunction "SHIELD_S3") (pintype "bidirectional"))
      (node (ref "J5") (pin "S4") (pinfunction "SHIELD_S4") (pintype "bidirectional"))
      (node (ref "J7") (pin "1") (pinfunction "1_1") (pintype "passive"))
      (node (ref "J8") (pin "1") (pinfunction "GND_1") (pintype "bidirectional"))
      (node (ref "J8") (pin "2") (pinfunction "GND_2") (pintype "bidirectional"))
      (node (ref "JP1") (pin "1") (pinfunction "1_1") (pintype "passive"))
      (node (ref "PMIC1") (pin "1") (pinfunction "GND_1") (pintype "bidirectional"))
      (node (ref "PMIC2") (pin "1") (pinfunction "GND_1") (pintype "bidirectional"))
      (node (ref "Q1") (pin "2") (pinfunction "S_2") (pintype "bidirectional"))
      (node (ref "R11") (pin "2") (pinfunction "2_2") (pintype "passive"))
      (node (ref "R19") (pin "2") (pinfunction "2_2") (pintype "passive"))
      (node (ref "R25") (pin "2") (pinfunction "2_2") (pintype "passive"))
      (node (ref "R29") (pin "2") (pinfunction "2_2") (pintype "passive"))
      (node (ref "R31") (pin "2") (pinfunction "2_2") (pintype "passive"))
      (node (ref "R6") (pin "1") (pinfunction "1_1") (pintype "passive"))
      (node (ref "R9") (pin "2") (pinfunction "2_2") (pintype "passive"))
      (node (ref "S2") (pin "2") (pinfunction "2_2") (pintype "passive"))
      (node (ref "U1") (pin "13") (pinfunction "GND_13") (pintype "passive"))
      (node (ref "U1") (pin "14") (pinfunction "GND_14") (pintype "passive"))
      (node (ref "U1") (pin "15") (pinfunction "GND_15") (pintype "passive"))
      (node (ref "U1") (pin "16") (pinfunction "GND_16") (pintype "passive"))
      (node (ref "U1") (pin "17") (pinfunction "GND_17") (pintype "passive"))
      (node (ref "U2") (pin "10") (pinfunction "GND_10") (pintype "bidirectional"))
      (node (ref "U2") (pin "12") (pinfunction "GND_12") (pintype "bidirectional"))
      (node (ref "U2") (pin "16") (pinfunction "GND_16") (pintype "bidirectional"))
      (node (ref "U2") (pin "4") (pinfunction "GND_4") (pintype "bidirectional"))
      (node (ref "U2") (pin "6") (pinfunction "GND_6") (pintype "bidirectional"))
      (node (ref "U2") (pin "EXT") (pinfunction "GND_EXT") (pintype "bidirectional"))
      (node (ref "U3") (pin "11") (pinfunction "GND_11") (pintype "power_in"))
      (node (ref "U4") (pin "18") (pinfunction "GND_18") (pintype "bidirectional"))
      (node (ref "U4") (pin "35") (pinfunction "GND_35") (pintype "bidirectional"))
      (node (ref "U4") (pin "42") (pinfunction "GND_42") (pintype "bidirectional"))
      (node (ref "U4") (pin "5") (pinfunction "GNDANA_5") (pintype "bidirectional"))
      (node (ref "U6") (pin "10") (pinfunction "ADDR1_10") (pintype "bidirectional"))
      (node (ref "U6") (pin "17") (pinfunction "GND_17") (pintype "bidirectional"))
      (node (ref "U6") (pin "26") (pinfunction "ADDR0_26") (pintype "bidirectional"))
      (node (ref "U6") (pin "29") (pinfunction "GND_29") (pintype "bidirectional"))
      (node (ref "U6") (pin "3") (pinfunction "GND_3") (pintype "bidirectional"))
      (node (ref "U7") (pin "6") (pinfunction "GND_6") (pintype "power_in"))
      (node (ref "U8") (pin "3") (pinfunction "GND_3") (pintype "passive"))
      (node (ref "U8") (pin "P$1") (pinfunction "GND_P$1") (pintype "passive"))
      (node (ref "X1") (pin "P$1") (pinfunction "1_P$1") (pintype "passive"))
      (node (ref "X2") (pin "GND1") (pinfunction "GND1_GND1") (pintype "power_in"))
      (node (ref "X2") (pin "GND2") (pinfunction "GND2_GND2") (pintype "power_in"))
      (node (ref "X2") (pin "GND3") (pinfunction "GND3_GND3") (pintype "power_in"))
      (node (ref "X2") (pin "GND4") (pinfunction "GND4_GND4") (pintype "power_in"))
    )
    (net (code "19") (name "IO-CTS") (class "Default")
      (node (ref "U3") (pin "14") (pinfunction "B6_14") (pintype "bidirectional"))
      (node (ref "U4") (pin "13") (pinfunction "PA08(I2C/AIN16/SER0:0+)_13") (pintype "bidirectional"))
    )
    (net (code "20") (name "IO-DCD") (class "Default")
      (node (ref "U3") (pin "17") (pinfunction "B3_17") (pintype "bidirectional"))
      (node (ref "U4") (pin "25") (pinfunction "PA16(I2C/SER1:0+)_25") (pintype "bidirectional"))
    )
    (net (code "21") (name "IO-DSR") (class "Default")
      (node (ref "U3") (pin "15") (pinfunction "B5_15") (pintype "bidirectional"))
      (node (ref "U4") (pin "23") (pinfunction "PA14(XIN/SER2:2+)_23") (pintype "bidirectional"))
    )
    (net (code "22") (name "IO-DTR") (class "Default")
      (node (ref "U3") (pin "20") (pinfunction "B1_20") (pintype "bidirectional"))
      (node (ref "U4") (pin "29") (pinfunction "PA20(SER5:2+)_29") (pintype "bidirectional"))
    )
    (net (code "23") (name "IO-RI") (class "Default")
      (node (ref "U3") (pin "18") (pinfunction "B2_18") (pintype "bidirectional"))
      (node (ref "U4") (pin "27") (pinfunction "PA18(SER1:2+)_27") (pintype "bidirectional"))
    )
    (net (code "24") (name "IO-RTS") (class "Default")
      (node (ref "U3") (pin "16") (pinfunction "B4_16") (pintype "bidirectional"))
      (node (ref "U4") (pin "24") (pinfunction "PA15(XOUT/SER2:3+)_24") (pintype "bidirectional"))
    )
    (net (code "25") (name "IO-RX") (class "Default")
      (node (ref "U3") (pin "13") (pinfunction "B7_13") (pintype "bidirectional"))
      (node (ref "U4") (pin "16") (pinfunction "PA11(AIN19/SER0:3+)_16") (pintype "bidirectional"))
    )
    (net (code "26") (name "IO-TX") (class "Default")
      (node (ref "U3") (pin "12") (pinfunction "B8_12") (pintype "bidirectional"))
      (node (ref "U4") (pin "15") (pinfunction "PA10(AIN18/SER0:2+)_15") (pintype "bidirectional"))
    )
    (net (code "27") (name "IR_BOOST") (class "Default")
      (node (ref "C7") (pin "+") (pinfunction "+_+") (pintype "passive"))
      (node (ref "C8") (pin "+") (pinfunction "+_+") (pintype "passive"))
      (node (ref "C9") (pin "1") (pinfunction "1_1") (pintype "passive"))
      (node (ref "L1") (pin "1") (pinfunction "1_1") (pintype "passive"))
      (node (ref "PMIC2") (pin "TAB") (pinfunction "OUT_TAB") (pintype "bidirectional"))
      (node (ref "R4") (pin "1") (pinfunction "1_1") (pintype "passive"))
      (node (ref "U1") (pin "27") (pinfunction "VIN_27") (pintype "passive"))
    )
    (net (code "28") (name "IR_SIM_CLK") (class "Default")
      (node (ref "J1") (pin "24") (pinfunction "SIM_CLOCK_24") (pintype "bidirectional"))
      (node (ref "U2") (pin "13") (pinfunction "CLK_13") (pintype "bidirectional"))
    )
    (net (code "29") (name "IR_SIM_EN") (class "Default")
      (node (ref "J1") (pin "25") (pinfunction "SIM_ENABLE_25") (pintype "bidirectional"))
      (node (ref "JP4") (pin "3") (pinfunction "3_3") (pintype "passive"))
      (node (ref "TP9") (pin "P$1") (pinfunction "1_P$1") (pintype "bidirectional"))
    )
    (net (code "30") (name "IR_SIM_IO") (class "Default")
      (node (ref "J1") (pin "27") (pinfunction "SIM_DATA_IO_27") (pintype "bidirectional"))
      (node (ref "U2") (pin "15") (pinfunction "I/O_15") (pintype "bidirectional"))
    )
    (net (code "31") (name "IR_SIM_RST") (class "Default")
      (node (ref "J1") (pin "26") (pinfunction "SIM_RESET_26") (pintype "bidirectional"))
      (node (ref "U2") (pin "14") (pinfunction "RST_14") (pintype "bidirectional"))
    )
    (net (code "32") (name "IR_SIM_V") (class "Default")
      (node (ref "J1") (pin "23") (pinfunction "SIM_1V8_3V_23") (pintype "bidirectional"))
      (node (ref "U2") (pin "2") (pinfunction "MOD_VCC_2") (pintype "bidirectional"))
    )
    (net (code "33") (name "MODE_SW") (class "Default")
      (node (ref "J1") (pin "30") (pinfunction "LBT_HSTB_30") (pintype "bidirectional"))
      (node (ref "JP1") (pin "2") (pinfunction "2_2") (pintype "passive"))
    )
    (net (code "34") (name "Net-(C3-Pad1)") (class "Default")
      (node (ref "C3") (pin "1") (pinfunction "1_1") (pintype "passive"))
      (node (ref "R2") (pin "1") (pinfunction "1_1") (pintype "passive"))
    )
    (net (code "35") (name "Net-(D1-Pad1)") (class "Default")
      (node (ref "D1") (pin "1") (pinfunction "1_1") (pintype "passive"))
      (node (ref "D1") (pin "2") (pinfunction "2_2") (pintype "passive"))
      (node (ref "L1") (pin "2") (pinfunction "2_2") (pintype "passive"))
      (node (ref "U1") (pin "10") (pinfunction "NC_10") (pintype "passive"))
      (node (ref "U1") (pin "20") (pinfunction "SW_20") (pintype "passive"))
      (node (ref "U1") (pin "21") (pinfunction "SW_21") (pintype "passive"))
      (node (ref "U1") (pin "38") (pinfunction "SW_38") (pintype "passive"))
      (node (ref "U1") (pin "8") (pinfunction "SW_8") (pintype "passive"))
      (node (ref "U1") (pin "9") (pinfunction "SW_9") (pintype "passive"))
    )
    (net (code "36") (name "Net-(J8-SIGNAL)") (class "Default")
      (node (ref "J8") (pin "FEED") (pinfunction "SIGNAL_FEED") (pintype "bidirectional"))
      (node (ref "X2") (pin "ANTENNA") (pinfunction "ANT_ANTENNA") (pintype "bidirectional"))
    )
    (net (code "37") (name "Net-(JP1-Pad3)") (class "Default")
      (node (ref "JP1") (pin "3") (pinfunction "3_3") (pintype "passive"))
      (node (ref "JP2") (pin "2") (pinfunction "2_2") (pintype "passive"))
    )
    (net (code "38") (name "Net-(LED1-PadA)") (class "Default")
      (node (ref "LED1") (pin "A") (pinfunction "A_A") (pintype "passive"))
      (node (ref "R8") (pin "2") (pinfunction "2_2") (pintype "passive"))
    )
    (net (code "39") (name "Net-(PMIC1-IN)") (class "Default")
      (node (ref "PMIC1") (pin "2") (pinfunction "IN_2") (pintype "bidirectional"))
      (node (ref "R22") (pin "2") (pinfunction "2_2") (pintype "passive"))
    )
    (net (code "40") (name "Net-(PMIC1-IS)") (class "Default")
      (node (ref "PMIC1") (pin "4") (pinfunction "IS_4") (pintype "bidirectional"))
      (node (ref "R23") (pin "2") (pinfunction "2_2") (pintype "passive"))
      (node (ref "R25") (pin "1") (pinfunction "1_1") (pintype "passive"))
    )
    (net (code "41") (name "Net-(PMIC2-IN)") (class "Default")
      (node (ref "PMIC2") (pin "2") (pinfunction "IN_2") (pintype "bidirectional"))
      (node (ref "R26") (pin "2") (pinfunction "2_2") (pintype "passive"))
    )
    (net (code "42") (name "Net-(PMIC2-IS)") (class "Default")
      (node (ref "PMIC2") (pin "4") (pinfunction "IS_4") (pintype "bidirectional"))
      (node (ref "R27") (pin "2") (pinfunction "2_2") (pintype "passive"))
      (node (ref "R29") (pin "1") (pinfunction "1_1") (pintype "passive"))
    )
    (net (code "43") (name "Net-(Q1-D)") (class "Default")
      (node (ref "LED1") (pin "C") (pinfunction "C_C") (pintype "passive"))
      (node (ref "Q1") (pin "3") (pinfunction "D_3") (pintype "bidirectional"))
    )
    (net (code "44") (name "Net-(S1-P)") (class "Default")
      (node (ref "JP3") (pin "2") (pinfunction "2_2") (pintype "passive"))
      (node (ref "S1") (pin "2") (pinfunction "P_2") (pintype "passive"))
    )
    (net (code "45") (name "Net-(U1-EN{slash}UVLO)") (class "Default")
      (node (ref "R3") (pin "2") (pinfunction "2_2") (pintype "passive"))
      (node (ref "U1") (pin "25") (pinfunction "EN/UVLO_25") (pintype "passive"))
    )
    (net (code "46") (name "Net-(U1-FBX)") (class "Default")
      (node (ref "R5") (pin "2") (pinfunction "2_2") (pintype "passive"))
      (node (ref "R7") (pin "2") (pinfunction "2_2") (pintype "passive"))
      (node (ref "U1") (pin "31") (pinfunction "FBX_31") (pintype "passive"))
    )
    (net (code "47") (name "Net-(U1-INTVCC)") (class "Default")
      (node (ref "C2") (pin "2") (pinfunction "2_2") (pintype "passive"))
      (node (ref "U1") (pin "36") (pinfunction "INTVCC_36") (pintype "passive"))
    )
    (net (code "48") (name "Net-(U1-RT)") (class "Default")
      (node (ref "R1") (pin "2") (pinfunction "2_2") (pintype "passive"))
      (node (ref "U1") (pin "33") (pinfunction "RT_33") (pintype "passive"))
    )
    (net (code "49") (name "Net-(U1-SS)") (class "Default")
      (node (ref "C1") (pin "1") (pinfunction "1_1") (pintype "passive"))
      (node (ref "U1") (pin "32") (pinfunction "SS_32") (pintype "passive"))
    )
    (net (code "50") (name "Net-(U1-VC)") (class "Default")
      (node (ref "C4") (pin "1") (pinfunction "1_1") (pintype "passive"))
      (node (ref "R2") (pin "2") (pinfunction "2_2") (pintype "passive"))
      (node (ref "U1") (pin "30") (pinfunction "VC_30") (pintype "passive"))
    )
    (net (code "51") (name "Net-(U2-~{STOP})") (class "Default")
      (node (ref "JP4") (pin "2") (pinfunction "2_2") (pintype "passive"))
      (node (ref "U2") (pin "1") (pinfunction "~{STOP}_1") (pintype "bidirectional"))
    )
    (net (code "52") (name "Net-(U3-VCCA)") (class "Default")
      (node (ref "C22") (pin "2") (pinfunction "2_2") (pintype "passive"))
      (node (ref "JP5") (pin "2") (pinfunction "2_2") (pintype "passive"))
      (node (ref "U3") (pin "2") (pinfunction "VCCA_2") (pintype "power_in"))
    )
    (net (code "53") (name "Net-(U4-PA00(XIN32{slash}SER1:0{slash}TC2:0))") (class "Default")
      (node (ref "C25") (pin "1") (pinfunction "1_1") (pintype "passive"))
      (node (ref "U4") (pin "1") (pinfunction "PA00(XIN32/SER1:0/TC2:0)_1") (pintype "bidirectional"))
      (node (ref "Y1") (pin "P$2") (pinfunction "2_P$2") (pintype "passive"))
    )
    (net (code "54") (name "Net-(U4-PA01(XOUT32{slash}SER1:1{slash}TC2:1))") (class "Default")
      (node (ref "C26") (pin "1") (pinfunction "1_1") (pintype "passive"))
      (node (ref "U4") (pin "2") (pinfunction "PA01(XOUT32/SER1:1/TC2:1)_2") (pintype "bidirectional"))
      (node (ref "Y1") (pin "P$1") (pinfunction "1_P$1") (pintype "passive"))
    )
    (net (code "55") (name "Net-(U4-VDDANA)") (class "Default")
      (node (ref "C24") (pin "1") (pinfunction "1_1") (pintype "passive"))
      (node (ref "FB1") (pin "1") (pinfunction "1_1") (pintype "passive"))
      (node (ref "U4") (pin "6") (pinfunction "VDDANA_6") (pintype "bidirectional"))
    )
    (net (code "56") (name "Net-(U4-VDDCORE)") (class "Default")
      (node (ref "C21") (pin "1") (pinfunction "1_1") (pintype "passive"))
      (node (ref "U4") (pin "43") (pinfunction "VDDCORE_43") (pintype "bidirectional"))
    )
    (net (code "57") (name "Net-(U6-~{INT})") (class "Default")
      (node (ref "R17") (pin "2") (pinfunction "2_2") (pintype "passive"))
      (node (ref "U6") (pin "9") (pinfunction "~{INT}_9") (pintype "bidirectional"))
    )
    (net (code "58") (name "Net-(U6-~{RESET})") (class "Default")
      (node (ref "R18") (pin "2") (pinfunction "2_2") (pintype "passive"))
      (node (ref "U6") (pin "23") (pinfunction "~{RESET}_23") (pintype "bidirectional"))
    )
    (net (code "59") (name "Net-(U7-VCCB)") (class "Default")
      (node (ref "C33") (pin "2") (pinfunction "2_2") (pintype "passive"))
      (node (ref "J3") (pin "2") (pinfunction "2_2") (pintype "passive"))
      (node (ref "U7") (pin "11") (pinfunction "VCCB_11") (pintype "power_in"))
    )
    (net (code "60") (name "Net-(U8-PWRGD)") (class "Default")
      (node (ref "R30") (pin "1") (pinfunction "1_1") (pintype "passive"))
      (node (ref "U8") (pin "5") (pinfunction "PWRGD_5") (pintype "passive"))
    )
    (net (code "61") (name "PWR_EN") (class "Default")
      (node (ref "J1") (pin "32") (pinfunction "TRX_ON_32") (pintype "bidirectional"))
      (node (ref "U6") (pin "20") (pinfunction "I/O[13]_20") (pintype "bidirectional"))
    )
    (net (code "62") (name "PWR_SW") (class "Default")
      (node (ref "R31") (pin "1") (pinfunction "1_1") (pintype "passive"))
      (node (ref "S3") (pin "2") (pinfunction "P_2") (pintype "passive"))
      (node (ref "U6") (pin "21") (pinfunction "I/O[14]_21") (pintype "bidirectional"))
    )
    (net (code "63") (name "RF_EN") (class "Default")
      (node (ref "J1") (pin "28") (pinfunction "FULL_POWER_EN_28") (pintype "bidirectional"))
      (node (ref "Q1") (pin "1") (pinfunction "G_1") (pintype "bidirectional"))
      (node (ref "R9") (pin "1") (pinfunction "1_1") (pintype "passive"))
      (node (ref "S1") (pin "1") (pinfunction "O_1") (pintype "passive"))
      (node (ref "TP6") (pin "P$1") (pinfunction "1_P$1") (pintype "bidirectional"))
    )
    (net (code "64") (name "RI") (class "Default")
      (node (ref "J1") (pin "20") (pinfunction "DF_RI_20") (pintype "bidirectional"))
      (node (ref "U3") (pin "3") (pinfunction "A2_3") (pintype "bidirectional"))
    )
    (net (code "65") (name "RTS") (class "Default")
      (node (ref "J1") (pin "21") (pinfunction "DF_RTS_21") (pintype "bidirectional"))
      (node (ref "U3") (pin "5") (pinfunction "A4_5") (pintype "bidirectional"))
    )
    (net (code "66") (name "RX") (class "Default")
      (node (ref "J1") (pin "15") (pinfunction "DF_RX_15") (pintype "bidirectional"))
      (node (ref "U3") (pin "8") (pinfunction "A7_8") (pintype "bidirectional"))
    )
    (net (code "67") (name "SCL") (class "Default")
      (node (ref "R21") (pin "2") (pinfunction "2_2") (pintype "passive"))
      (node (ref "U4") (pin "32") (pinfunction "PA23(I2C/SER3:0+)_32") (pintype "bidirectional"))
      (node (ref "U6") (pin "25") (pinfunction "SCL_25") (pintype "bidirectional"))
    )
    (net (code "68") (name "SDA") (class "Default")
      (node (ref "R20") (pin "2") (pinfunction "2_2") (pintype "passive"))
      (node (ref "U4") (pin "31") (pinfunction "PA22(I2C/SER3:0+)_31") (pintype "bidirectional"))
      (node (ref "U6") (pin "24") (pinfunction "SDA_24") (pintype "bidirectional"))
    )
    (net (code "69") (name "SIM_CLK") (class "Default")
      (node (ref "J2") (pin "C3") (pinfunction "CLK_C3") (pintype "input"))
      (node (ref "U2") (pin "11") (pinfunction "SIM_CLK_11") (pintype "bidirectional"))
    )
    (net (code "70") (name "SIM_IO") (class "Default")
      (node (ref "J2") (pin "C7") (pinfunction "I/O_C7") (pintype "bidirectional"))
      (node (ref "U2") (pin "8") (pinfunction "SIM_I/O_8") (pintype "bidirectional"))
    )
    (net (code "71") (name "SIM_RST") (class "Default")
      (node (ref "J2") (pin "C2") (pinfunction "RST_C2") (pintype "input"))
      (node (ref "U2") (pin "9") (pinfunction "SIM_RST_9") (pintype "bidirectional"))
    )
    (net (code "72") (name "SIM_VCC") (class "Default")
      (node (ref "C15") (pin "2") (pinfunction "2_2") (pintype "passive"))
      (node (ref "J2") (pin "C1") (pinfunction "VCC_C1") (pintype "power_in"))
      (node (ref "U2") (pin "7") (pinfunction "SIM_VCC_7") (pintype "bidirectional"))
    )
    (net (code "73") (name "SWCLK") (class "Default")
      (node (ref "J4") (pin "4") (pinfunction "SWDCLK/TCK_4") (pintype "bidirectional"))
      (node (ref "U4") (pin "45") (pinfunction "PA30(SWCLK/SER1:2+)_45") (pintype "bidirectional"))
    )
    (net (code "74") (name "SWDIO") (class "Default")
      (node (ref "J4") (pin "2") (pinfunction "SWDIO/TMS_2") (pintype "bidirectional"))
      (node (ref "U4") (pin "46") (pinfunction "PA31(SWDIO/SER1:3+)_46") (pintype "bidirectional"))
    )
    (net (code "75") (name "SYS-RX") (class "Default")
      (node (ref "U4") (pin "38") (pinfunction "PB23(SER5:3+)_38") (pintype "bidirectional"))
      (node (ref "U7") (pin "3") (pinfunction "A2_3") (pintype "bidirectional"))
    )
    (net (code "76") (name "SYS-TX") (class "Default")
      (node (ref "U4") (pin "37") (pinfunction "PB22(SER5:2+)_37") (pintype "bidirectional"))
      (node (ref "U7") (pin "2") (pinfunction "A1_2") (pintype "bidirectional"))
    )
    (net (code "77") (name "SYS_SPARE") (class "Default")
      (node (ref "U7") (pin "4") (pinfunction "A3_4") (pintype "bidirectional"))
    )
    (net (code "78") (name "TES-EN") (class "Default")
      (node (ref "CR2") (pin "1") (pinfunction "2_1") (pintype "passive"))
      (node (ref "J7") (pin "3") (pinfunction "3_3") (pintype "passive"))
      (node (ref "U8") (pin "1") (pinfunction "~{SHDN}_1") (pintype "passive"))
    )
    (net (code "79") (name "TES-GPS-FLAG") (class "Default")
      (node (ref "J7") (pin "4") (pinfunction "4_4") (pintype "passive"))
      (node (ref "U7") (pin "7") (pinfunction "B4_7") (pintype "bidirectional"))
    )
    (net (code "80") (name "TES-RX") (class "Default")
      (node (ref "J7") (pin "5") (pinfunction "5_5") (pintype "passive"))
      (node (ref "U7") (pin "9") (pinfunction "B2_9") (pintype "bidirectional"))
    )
    (net (code "81") (name "TES-SPARE") (class "Default")
      (node (ref "U7") (pin "8") (pinfunction "B3_8") (pintype "bidirectional"))
    )
    (net (code "82") (name "TES-TX") (class "Default")
      (node (ref "J7") (pin "6") (pinfunction "6_6") (pintype "passive"))
      (node (ref "U7") (pin "10") (pinfunction "B1_10") (pintype "bidirectional"))
    )
    (net (code "83") (name "TX") (class "Default")
      (node (ref "J1") (pin "16") (pinfunction "DF_TX_16") (pintype "bidirectional"))
      (node (ref "U3") (pin "9") (pinfunction "A8_9") (pintype "bidirectional"))
    )
    (net (code "84") (name "TX_ACTIVE") (class "Default")
      (node (ref "J1") (pin "31") (pinfunction "TX_ACTIVE_31") (pintype "bidirectional"))
      (node (ref "TP10") (pin "P$1") (pinfunction "1_P$1") (pintype "bidirectional"))
      (node (ref "U6") (pin "15") (pinfunction "I/O[10]_15") (pintype "bidirectional"))
      (node (ref "U7") (pin "5") (pinfunction "A4_5") (pintype "bidirectional"))
    )
    (net (code "85") (name "USB_D+") (class "Default")
      (node (ref "J5") (pin "D+") (pinfunction "D+_D+") (pintype "bidirectional"))
      (node (ref "U4") (pin "34") (pinfunction "PA25(SER3:3+)_34") (pintype "bidirectional"))
    )
    (net (code "86") (name "USB_D-") (class "Default")
      (node (ref "J5") (pin "D-") (pinfunction "D-_D-") (pintype "bidirectional"))
      (node (ref "U4") (pin "33") (pinfunction "PA24(SER3:2+)_33") (pintype "bidirectional"))
    )
    (net (code "87") (name "VBAT") (class "Default")
      (node (ref "C40") (pin "1") (pinfunction "1_1") (pintype "passive"))
      (node (ref "CR1") (pin "1") (pinfunction "ANODE1_1") (pintype "passive"))
      (node (ref "PMIC2") (pin "5") (pinfunction "VS_5") (pintype "bidirectional"))
      (node (ref "X1") (pin "P$2") (pinfunction "2_P$2") (pintype "passive"))
    )
    (net (code "88") (name "VBUS") (class "Default")
      (node (ref "J5") (pin "VBUS") (pinfunction "VBUS_VBUS") (pintype "power_in"))
    )
    (net (code "89") (name "VCC") (class "Default")
      (node (ref "C10") (pin "+") (pinfunction "+_+") (pintype "passive"))
      (node (ref "C11") (pin "+") (pinfunction "+_+") (pintype "passive"))
      (node (ref "C12") (pin "+") (pinfunction "+_+") (pintype "passive"))
      (node (ref "C13") (pin "+") (pinfunction "+_+") (pintype "passive"))
      (node (ref "C14") (pin "1") (pinfunction "1_1") (pintype "passive"))
      (node (ref "C5") (pin "2") (pinfunction "2_2") (pintype "passive"))
      (node (ref "D1") (pin "3") (pinfunction "3_3") (pintype "passive"))
      (node (ref "J1") (pin "37") (pinfunction "VBOOST_37") (pintype "bidirectional"))
      (node (ref "J1") (pin "39") (pinfunction "VBOOST_39") (pintype "bidirectional"))
      (node (ref "R7") (pin "1") (pinfunction "1_1") (pintype "passive"))
      (node (ref "U1") (pin "28") (pinfunction "DRIVE_28") (pintype "passive"))
    )
    (net (code "90") (name "V_BATT") (class "Default")
      (node (ref "C16") (pin "2") (pinfunction "2_2") (pintype "passive"))
      (node (ref "C37") (pin "1") (pinfunction "1_1") (pintype "passive"))
      (node (ref "C6") (pin "2") (pinfunction "2_2") (pintype "passive"))
      (node (ref "J1") (pin "36") (pinfunction "VBAT_36") (pintype "bidirectional"))
      (node (ref "J1") (pin "38") (pinfunction "VBAT_38") (pintype "bidirectional"))
      (node (ref "J1") (pin "40") (pinfunction "VBAT_40") (pintype "bidirectional"))
      (node (ref "JP4") (pin "1") (pinfunction "1_1") (pintype "passive"))
      (node (ref "PMIC1") (pin "TAB") (pinfunction "OUT_TAB") (pintype "bidirectional"))
      (node (ref "R8") (pin "1") (pinfunction "1_1") (pintype "passive"))
      (node (ref "U2") (pin "3") (pinfunction "VDD_3") (pintype "bidirectional"))
      (node (ref "U2") (pin "5") (pinfunction "VBAT_5") (pintype "bidirectional"))
    )
    (net (code "91") (name "unconnected-(J1-CODEC_PCMCLK-Pad1)") (class "Default")
      (node (ref "J1") (pin "1") (pinfunction "CODEC_PCMCLK_1") (pintype "bidirectional"))
    )
    (net (code "92") (name "unconnected-(J1-CODEC_PCMIN-Pad2)") (class "Default")
      (node (ref "J1") (pin "2") (pinfunction "CODEC_PCMIN_2") (pintype "bidirectional"))
    )
    (net (code "93") (name "unconnected-(J1-CODEC_PCMOUT-Pad4)") (class "Default")
      (node (ref "J1") (pin "4") (pinfunction "CODEC_PCMOUT_4") (pintype "bidirectional"))
    )
    (net (code "94") (name "unconnected-(J1-CODEC_PCMSYNC-Pad3)") (class "Default")
      (node (ref "J1") (pin "3") (pinfunction "CODEC_PCMSYNC_3") (pintype "bidirectional"))
    )
    (net (code "95") (name "unconnected-(J1-DPL_RXD-Pad13)") (class "Default")
      (node (ref "J1") (pin "13") (pinfunction "DPL_RXD_13") (pintype "bidirectional"))
    )
    (net (code "96") (name "unconnected-(J1-DPL_TXD-Pad14)") (class "Default")
      (node (ref "J1") (pin "14") (pinfunction "DPL_TXD_14") (pintype "bidirectional"))
    )
    (net (code "97") (name "unconnected-(J1-UC_DACLK-Pad7)") (class "Default")
      (node (ref "J1") (pin "7") (pinfunction "UC_DACLK_7") (pintype "bidirectional"))
    )
    (net (code "98") (name "unconnected-(J1-UC_DAFS-Pad9)") (class "Default")
      (node (ref "J1") (pin "9") (pinfunction "UC_DAFS_9") (pintype "bidirectional"))
    )
    (net (code "99") (name "unconnected-(J1-UC_DARX-Pad10)") (class "Default")
      (node (ref "J1") (pin "10") (pinfunction "UC_DARX_10") (pintype "bidirectional"))
    )
    (net (code "100") (name "unconnected-(J1-UC_DATX-Pad8)") (class "Default")
      (node (ref "J1") (pin "8") (pinfunction "UC_DATX_8") (pintype "bidirectional"))
    )
    (net (code "101") (name "unconnected-(J2-VPP-PadC6)") (class "Default")
      (node (ref "J2") (pin "C6") (pinfunction "VPP_C6") (pintype "input"))
    )
    (net (code "102") (name "unconnected-(J4-GNDDTCT-Pad9)") (class "Default")
      (node (ref "J4") (pin "9") (pinfunction "GNDDTCT_9") (pintype "bidirectional"))
    )
    (net (code "103") (name "unconnected-(J4-KEY-Pad7)") (class "Default")
      (node (ref "J4") (pin "7") (pinfunction "KEY_7") (pintype "bidirectional"))
    )
    (net (code "104") (name "unconnected-(J4-NC{slash}TDI-Pad8)") (class "Default")
      (node (ref "J4") (pin "8") (pinfunction "NC/TDI_8") (pintype "bidirectional"))
    )
    (net (code "105") (name "unconnected-(J4-SWO{slash}TDO-Pad6)") (class "Default")
      (node (ref "J4") (pin "6") (pinfunction "SWO/TDO_6") (pintype "bidirectional"))
    )
    (net (code "106") (name "unconnected-(J5-PadID)") (class "Default")
      (node (ref "J5") (pin "ID") (pinfunction "ID_ID") (pintype "bidirectional"))
    )
    (net (code "107") (name "unconnected-(S1-S-Pad3)") (class "Default")
      (node (ref "S1") (pin "3") (pinfunction "S_3") (pintype "passive"))
    )
    (net (code "108") (name "unconnected-(S3-O-Pad1)") (class "Default")
      (node (ref "S3") (pin "1") (pinfunction "O_1") (pintype "passive"))
    )
    (net (code "109") (name "unconnected-(U4-PA02(AIN0{slash}DAC)-Pad3)") (class "Default")
      (node (ref "U4") (pin "3") (pinfunction "PA02(AIN0/DAC)_3") (pintype "bidirectional"))
    )
    (net (code "110") (name "unconnected-(U4-PA03(AIN1{slash}REFA)-Pad4)") (class "Default")
      (node (ref "U4") (pin "4") (pinfunction "PA03(AIN1/REFA)_4") (pintype "bidirectional"))
    )
    (net (code "111") (name "unconnected-(U4-PA04(AIN4{slash}REFB{slash}SER0:0{slash}TC0:0)-Pad9)") (class "Default")
      (node (ref "U4") (pin "9") (pinfunction "PA04(AIN4/REFB/SER0:0/TC0:0)_9") (pintype "bidirectional"))
    )
    (net (code "112") (name "unconnected-(U4-PA05(AIN5{slash}SER0:1{slash}TC0:1)-Pad10)") (class "Default")
      (node (ref "U4") (pin "10") (pinfunction "PA05(AIN5/SER0:1/TC0:1)_10") (pintype "bidirectional"))
    )
    (net (code "113") (name "unconnected-(U4-PA06(AIN6{slash}SER0:2{slash}TC1:0)-Pad11)") (class "Default")
      (node (ref "U4") (pin "11") (pinfunction "PA06(AIN6/SER0:2/TC1:0)_11") (pintype "bidirectional"))
    )
    (net (code "114") (name "unconnected-(U4-PA07(AIN7{slash}SER0:3{slash}TC1:1)-Pad12)") (class "Default")
      (node (ref "U4") (pin "12") (pinfunction "PA07(AIN7/SER0:3/TC1:1)_12") (pintype "bidirectional"))
    )
    (net (code "115") (name "unconnected-(U4-PA09(I2C{slash}AIN17{slash}SER0:1+)-Pad14)") (class "Default")
      (node (ref "U4") (pin "14") (pinfunction "PA09(I2C/AIN17/SER0:1+)_14") (pintype "bidirectional"))
    )
    (net (code "116") (name "unconnected-(U4-PA12(I2C{slash}SER2:0+)-Pad21)") (class "Default")
      (node (ref "U4") (pin "21") (pinfunction "PA12(I2C/SER2:0+)_21") (pintype "bidirectional"))
    )
    (net (code "117") (name "unconnected-(U4-PA13(I2C{slash}SER2:1+)-Pad22)") (class "Default")
      (node (ref "U4") (pin "22") (pinfunction "PA13(I2C/SER2:1+)_22") (pintype "bidirectional"))
    )
    (net (code "118") (name "unconnected-(U4-PA17(I2C{slash}SER1:1+)-Pad26)") (class "Default")
      (node (ref "U4") (pin "26") (pinfunction "PA17(I2C/SER1:1+)_26") (pintype "bidirectional"))
    )
    (net (code "119") (name "unconnected-(U4-PA19(SER1:3+)-Pad28)") (class "Default")
      (node (ref "U4") (pin "28") (pinfunction "PA19(SER1:3+)_28") (pintype "bidirectional"))
    )
    (net (code "120") (name "unconnected-(U4-PA21(SER5:3+)-Pad30)") (class "Default")
      (node (ref "U4") (pin "30") (pinfunction "PA21(SER5:3+)_30") (pintype "bidirectional"))
    )
    (net (code "121") (name "unconnected-(U4-PA27-Pad39)") (class "Default")
      (node (ref "U4") (pin "39") (pinfunction "PA27_39") (pintype "bidirectional"))
    )
    (net (code "122") (name "unconnected-(U4-PA28-Pad41)") (class "Default")
      (node (ref "U4") (pin "41") (pinfunction "PA28_41") (pintype "bidirectional"))
    )
    (net (code "123") (name "unconnected-(U4-PB02(AIN10{slash}SER5:0)-Pad47)") (class "Default")
      (node (ref "U4") (pin "47") (pinfunction "PB02(AIN10/SER5:0)_47") (pintype "bidirectional"))
    )
    (net (code "124") (name "unconnected-(U4-PB03(AIN11{slash}SER5:1)-Pad48)") (class "Default")
      (node (ref "U4") (pin "48") (pinfunction "PB03(AIN11/SER5:1)_48") (pintype "bidirectional"))
    )
    (net (code "125") (name "unconnected-(U4-PB10(SER4:2+)-Pad19)") (class "Default")
      (node (ref "U4") (pin "19") (pinfunction "PB10(SER4:2+)_19") (pintype "bidirectional"))
    )
    (net (code "126") (name "unconnected-(U4-PB11(SER4:3+)-Pad20)") (class "Default")
      (node (ref "U4") (pin "20") (pinfunction "PB11(SER4:3+)_20") (pintype "bidirectional"))
    )
    (net (code "127") (name "unconnected-(U6-I{slash}O[4]-Pad5)") (class "Default")
      (node (ref "U6") (pin "5") (pinfunction "I/O[4]_5") (pintype "bidirectional"))
    )
    (net (code "128") (name "unconnected-(U6-I{slash}O[5]-Pad6)") (class "Default")
      (node (ref "U6") (pin "6") (pinfunction "I/O[5]_6") (pintype "bidirectional"))
    )
    (net (code "129") (name "unconnected-(U6-I{slash}O[6]-Pad7)") (class "Default")
      (node (ref "U6") (pin "7") (pinfunction "I/O[6]_7") (pintype "bidirectional"))
    )
    (net (code "130") (name "unconnected-(U6-I{slash}O[7]-Pad8)") (class "Default")
      (node (ref "U6") (pin "8") (pinfunction "I/O[7]_8") (pintype "bidirectional"))
    )
    (net (code "131") (name "unconnected-(U6-I{slash}O[8]-Pad13)") (class "Default")
      (node (ref "U6") (pin "13") (pinfunction "I/O[8]_13") (pintype "bidirectional"))
    )
    (net (code "132") (name "unconnected-(U6-I{slash}O[15]-Pad22)") (class "Default")
      (node (ref "U6") (pin "22") (pinfunction "I/O[15]_22") (pintype "bidirectional"))
    )
    (net (code "133") (name "unconnected-(U6-OSCIO-Pad11)") (class "Default")
      (node (ref "U6") (pin "11") (pinfunction "OSCIO_11") (pintype "bidirectional"))
    )
    (net (code "134") (name "~{RST}") (class "Default")
      (node (ref "J4") (pin "10") (pinfunction "~{RESET}_10") (pintype "bidirectional"))
      (node (ref "R10") (pin "2") (pinfunction "2_2") (pintype "passive"))
      (node (ref "S2") (pin "1") (pinfunction "1_1") (pintype "passive"))
      (node (ref "U4") (pin "40") (pinfunction "~{RESET}_40") (pintype "bidirectional"))
    )
  )
)
